# AMC_FMC_Carrier.net
KiCad netlist of a schematic drawn in Altium Designer
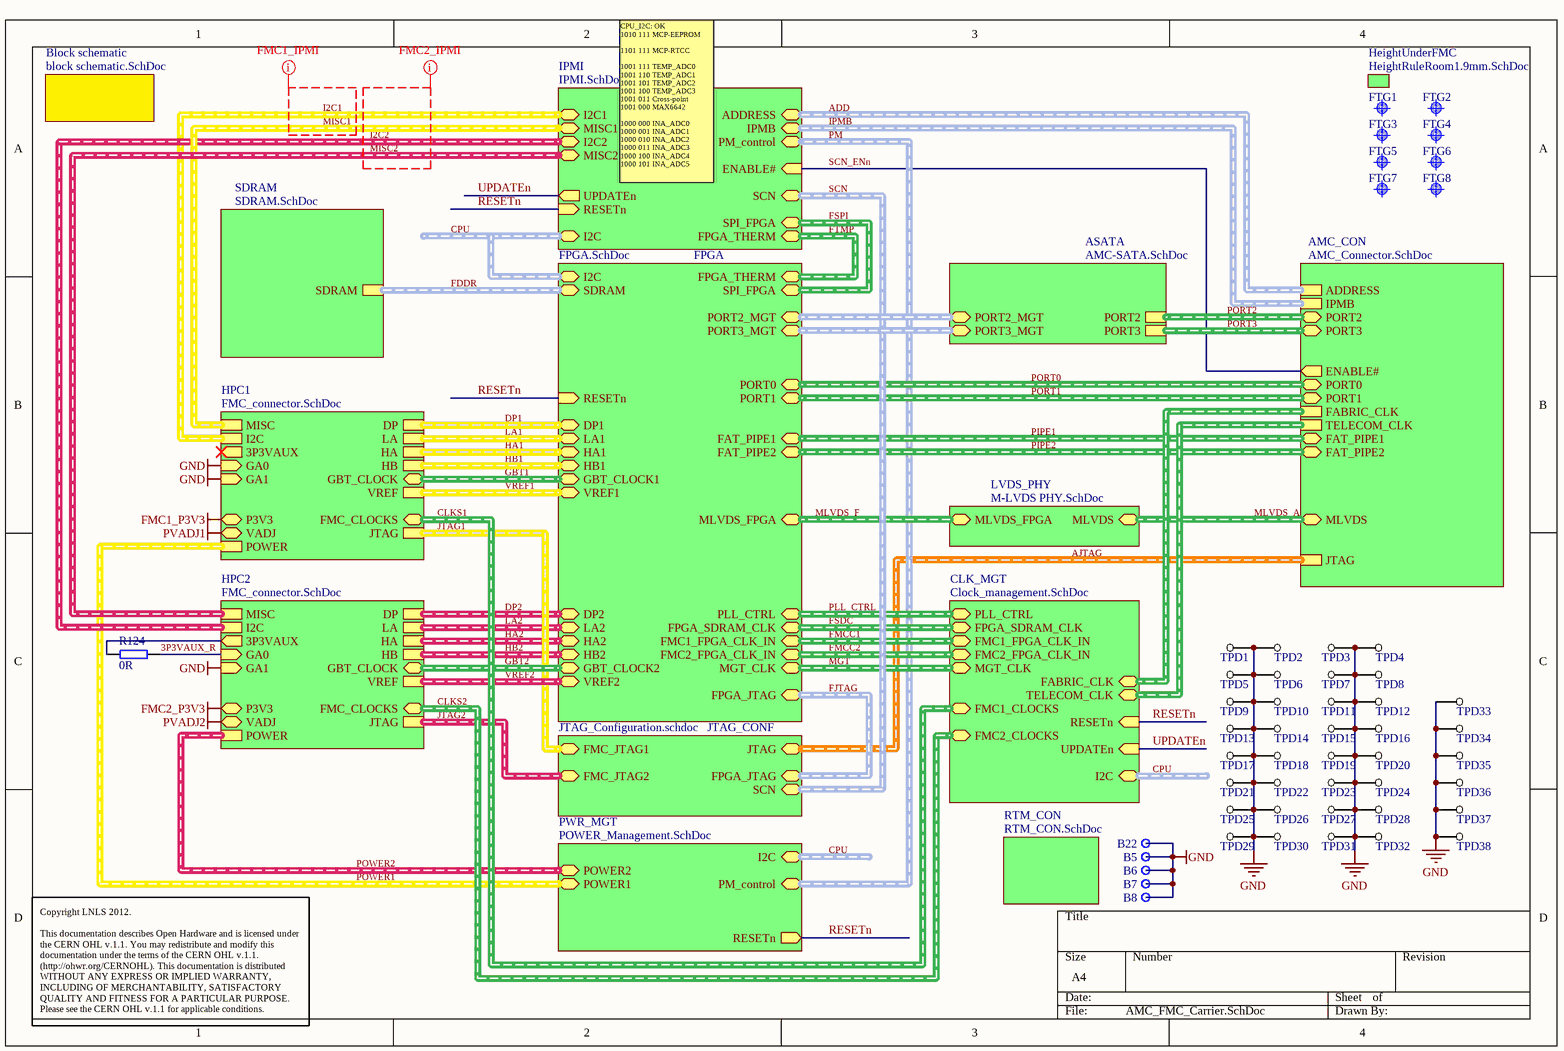
[diagram p0: AMC_FMC_Carrier.SchDoc]

(export (version "E")
  (design (tool "Eeschema 10.0.6"))
  (components
    (comp (ref "B5")
      (value "Test Point")
      (footprint "VERO_20-2136")
      (description "Single Terminal Socket")
      (fields
        (field (name "PART NUMBER") "VERO_20-2136")
        (field (name "MANUFACTURER") "VERO TECHNOLOGIES")
        (field (name "AUTHOR") "CERN DEM JLC")
      )
      (libsource (lib "Connectors") (part "Single Terminal Socket"))
    )
    (comp (ref "B6")
      (value "Test Point")
      (footprint "VERO_20-2136")
      (description "Single Terminal Socket")
      (fields
        (field (name "PART NUMBER") "VERO_20-2136")
        (field (name "MANUFACTURER") "VERO TECHNOLOGIES")
        (field (name "AUTHOR") "CERN DEM JLC")
      )
      (libsource (lib "Connectors") (part "Single Terminal Socket"))
    )
    (comp (ref "B7")
      (value "Test Point")
      (footprint "VERO_20-2136")
      (description "Single Terminal Socket")
      (fields
        (field (name "PART NUMBER") "VERO_20-2136")
        (field (name "MANUFACTURER") "VERO TECHNOLOGIES")
        (field (name "AUTHOR") "CERN DEM JLC")
      )
      (libsource (lib "Connectors") (part "Single Terminal Socket"))
    )
    (comp (ref "B8")
      (value "Test Point")
      (footprint "VERO_20-2136")
      (description "Single Terminal Socket")
      (fields
        (field (name "PART NUMBER") "VERO_20-2136")
        (field (name "MANUFACTURER") "VERO TECHNOLOGIES")
        (field (name "AUTHOR") "CERN DEM JLC")
      )
      (libsource (lib "Connectors") (part "Single Terminal Socket"))
    )
    (comp (ref "B22")
      (value "Test Point")
      (footprint "VERO_20-2136")
      (description "Single Terminal Socket")
      (fields
        (field (name "PART NUMBER") "VERO_20-2136")
        (field (name "MANUFACTURER") "VERO TECHNOLOGIES")
        (field (name "AUTHOR") "CERN DEM JLC")
      )
      (libsource (lib "Connectors") (part "Single Terminal Socket"))
    )
    (comp (ref "FTG1")
      (value "Use only in PCB")
      (footprint "FIDUCIAL_TOP_S100-200")
      (description "Fiducial Target")
      (fields (field (name "PART NUMBER") "FIDUCIAL_TARGET_S100-200") (field (name "AUTHOR") "CERN DEM JLC"))
      (libsource (lib "Eletro-mechanical") (part "Fiducial Target"))
    )
    (comp (ref "FTG2")
      (value "Use only in PCB")
      (footprint "FIDUCIAL_TOP_C100-200")
      (description "Fiducial Target")
      (fields (field (name "PART NUMBER") "FIDUCIAL_TARGET_C100-200") (field (name "AUTHOR") "CERN DEM JLC"))
      (libsource (lib "Eletro-mechanical") (part "Fiducial Target"))
    )
    (comp (ref "FTG3")
      (value "Use only in PCB")
      (footprint "FIDUCIAL_TOP_S100-200")
      (description "Fiducial Target")
      (fields (field (name "PART NUMBER") "FIDUCIAL_TARGET_S100-200") (field (name "AUTHOR") "CERN DEM JLC"))
      (libsource (lib "Eletro-mechanical") (part "Fiducial Target"))
    )
    (comp (ref "FTG4")
      (value "Use only in PCB")
      (footprint "FIDUCIAL_TOP_C100-200")
      (description "Fiducial Target")
      (fields (field (name "PART NUMBER") "FIDUCIAL_TARGET_C100-200") (field (name "AUTHOR") "CERN DEM JLC"))
      (libsource (lib "Eletro-mechanical") (part "Fiducial Target"))
    )
    (comp (ref "FTG5")
      (value "Use only in PCB")
      (footprint "FIDUCIAL_TOP_S100-200")
      (description "Fiducial Target")
      (fields (field (name "PART NUMBER") "FIDUCIAL_TARGET_S100-200") (field (name "AUTHOR") "CERN DEM JLC"))
      (libsource (lib "Eletro-mechanical") (part "Fiducial Target"))
    )
    (comp (ref "FTG6")
      (value "Use only in PCB")
      (footprint "FIDUCIAL_TOP_C100-200")
      (description "Fiducial Target")
      (fields (field (name "PART NUMBER") "FIDUCIAL_TARGET_C100-200") (field (name "AUTHOR") "CERN DEM JLC"))
      (libsource (lib "Eletro-mechanical") (part "Fiducial Target"))
    )
    (comp (ref "FTG7")
      (value "Use only in PCB")
      (footprint "FIDUCIAL_TOP_S100-200")
      (description "Fiducial Target")
      (fields (field (name "PART NUMBER") "FIDUCIAL_TARGET_S100-200") (field (name "AUTHOR") "CERN DEM JLC"))
      (libsource (lib "Eletro-mechanical") (part "Fiducial Target"))
    )
    (comp (ref "FTG8")
      (value "Use only in PCB")
      (footprint "FIDUCIAL_TOP_C100-200")
      (description "Fiducial Target")
      (fields (field (name "PART NUMBER") "FIDUCIAL_TARGET_C100-200") (field (name "AUTHOR") "CERN DEM JLC"))
      (libsource (lib "Eletro-mechanical") (part "Fiducial Target"))
    )
    (comp (ref "R124")
      (value "0R")
      (footprint "0402R")
      (description "SMD Resistor")
      (libsource (lib "LIBRARY_SCH") (part "RES_0402"))
    )
    (comp (ref "TPD1")
      (value "Test Point")
      (footprint "TP_DIFF_0805")
      (description "1625854-2")
      (fields (field (name "PART NUMBER") "TP_DIFF"))
      (libsource (lib "Markers") (part "TP_SMD_DIFF"))
    )
    (comp (ref "TPD2")
      (value "Test Point")
      (footprint "TP_DIFF_0805")
      (description "1625854-2")
      (fields (field (name "PART NUMBER") "TP_DIFF"))
      (libsource (lib "Markers") (part "TP_SMD_DIFF"))
    )
    (comp (ref "TPD3")
      (value "Test Point")
      (footprint "TP_DIFF_0805")
      (description "1625854-2")
      (fields (field (name "PART NUMBER") "TP_DIFF"))
      (libsource (lib "Markers") (part "TP_SMD_DIFF"))
    )
    (comp (ref "TPD4")
      (value "Test Point")
      (footprint "TP_DIFF_0805")
      (description "1625854-2")
      (fields (field (name "PART NUMBER") "TP_DIFF"))
      (libsource (lib "Markers") (part "TP_SMD_DIFF"))
    )
    (comp (ref "TPD5")
      (value "Test Point")
      (footprint "TP_DIFF_0805")
      (description "1625854-2")
      (fields (field (name "PART NUMBER") "TP_DIFF"))
      (libsource (lib "Markers") (part "TP_SMD_DIFF"))
    )
    (comp (ref "TPD6")
      (value "Test Point")
      (footprint "TP_DIFF_0805")
      (description "1625854-2")
      (fields (field (name "PART NUMBER") "TP_DIFF"))
      (libsource (lib "Markers") (part "TP_SMD_DIFF"))
    )
    (comp (ref "TPD7")
      (value "Test Point")
      (footprint "TP_DIFF_0805")
      (description "1625854-2")
      (fields (field (name "PART NUMBER") "TP_DIFF"))
      (libsource (lib "Markers") (part "TP_SMD_DIFF"))
    )
    (comp (ref "TPD8")
      (value "Test Point")
      (footprint "TP_DIFF_0805")
      (description "1625854-2")
      (fields (field (name "PART NUMBER") "TP_DIFF"))
      (libsource (lib "Markers") (part "TP_SMD_DIFF"))
    )
    (comp (ref "TPD9")
      (value "Test Point")
      (footprint "TP_DIFF_0805")
      (description "1625854-2")
      (fields (field (name "PART NUMBER") "TP_DIFF"))
      (libsource (lib "Markers") (part "TP_SMD_DIFF"))
    )
    (comp (ref "TPD10")
      (value "Test Point")
      (footprint "TP_DIFF_0805")
      (description "1625854-2")
      (fields (field (name "PART NUMBER") "TP_DIFF"))
      (libsource (lib "Markers") (part "TP_SMD_DIFF"))
    )
    (comp (ref "TPD11")
      (value "Test Point")
      (footprint "TP_DIFF_0805")
      (description "1625854-2")
      (fields (field (name "PART NUMBER") "TP_DIFF"))
      (libsource (lib "Markers") (part "TP_SMD_DIFF"))
    )
    (comp (ref "TPD12")
      (value "Test Point")
      (footprint "TP_DIFF_0805")
      (description "1625854-2")
      (fields (field (name "PART NUMBER") "TP_DIFF"))
      (libsource (lib "Markers") (part "TP_SMD_DIFF"))
    )
    (comp (ref "TPD13")
      (value "Test Point")
      (footprint "TP_DIFF_0805")
      (description "1625854-2")
      (fields (field (name "PART NUMBER") "TP_DIFF"))
      (libsource (lib "Markers") (part "TP_SMD_DIFF"))
    )
    (comp (ref "TPD14")
      (value "Test Point")
      (footprint "TP_DIFF_0805")
      (description "1625854-2")
      (fields (field (name "PART NUMBER") "TP_DIFF"))
      (libsource (lib "Markers") (part "TP_SMD_DIFF"))
    )
    (comp (ref "TPD15")
      (value "Test Point")
      (footprint "TP_DIFF_0805")
      (description "1625854-2")
      (fields (field (name "PART NUMBER") "TP_DIFF"))
      (libsource (lib "Markers") (part "TP_SMD_DIFF"))
    )
    (comp (ref "TPD16")
      (value "Test Point")
      (footprint "TP_DIFF_0805")
      (description "1625854-2")
      (fields (field (name "PART NUMBER") "TP_DIFF"))
      (libsource (lib "Markers") (part "TP_SMD_DIFF"))
    )
    (comp (ref "TPD17")
      (value "Test Point")
      (footprint "TP_DIFF_0805")
      (description "1625854-2")
      (fields (field (name "PART NUMBER") "TP_DIFF"))
      (libsource (lib "Markers") (part "TP_SMD_DIFF"))
    )
    (comp (ref "TPD18")
      (value "Test Point")
      (footprint "TP_DIFF_0805")
      (description "1625854-2")
      (fields (field (name "PART NUMBER") "TP_DIFF"))
      (libsource (lib "Markers") (part "TP_SMD_DIFF"))
    )
    (comp (ref "TPD19")
      (value "Test Point")
      (footprint "TP_DIFF_0805")
      (description "1625854-2")
      (fields (field (name "PART NUMBER") "TP_DIFF"))
      (libsource (lib "Markers") (part "TP_SMD_DIFF"))
    )
    (comp (ref "TPD20")
      (value "Test Point")
      (footprint "TP_DIFF_0805")
      (description "1625854-2")
      (fields (field (name "PART NUMBER") "TP_DIFF"))
      (libsource (lib "Markers") (part "TP_SMD_DIFF"))
    )
    (comp (ref "TPD21")
      (value "Test Point")
      (footprint "TP_DIFF_0805")
      (description "1625854-2")
      (fields (field (name "PART NUMBER") "TP_DIFF"))
      (libsource (lib "Markers") (part "TP_SMD_DIFF"))
    )
    (comp (ref "TPD22")
      (value "Test Point")
      (footprint "TP_DIFF_0805")
      (description "1625854-2")
      (fields (field (name "PART NUMBER") "TP_DIFF"))
      (libsource (lib "Markers") (part "TP_SMD_DIFF"))
    )
    (comp (ref "TPD23")
      (value "Test Point")
      (footprint "TP_DIFF_0805")
      (description "1625854-2")
      (fields (field (name "PART NUMBER") "TP_DIFF"))
      (libsource (lib "Markers") (part "TP_SMD_DIFF"))
    )
    (comp (ref "TPD24")
      (value "Test Point")
      (footprint "TP_DIFF_0805")
      (description "1625854-2")
      (fields (field (name "PART NUMBER") "TP_DIFF"))
      (libsource (lib "Markers") (part "TP_SMD_DIFF"))
    )
    (comp (ref "TPD25")
      (value "Test Point")
      (footprint "TP_DIFF_0805")
      (description "1625854-2")
      (fields (field (name "PART NUMBER") "TP_DIFF"))
      (libsource (lib "Markers") (part "TP_SMD_DIFF"))
    )
    (comp (ref "TPD26")
      (value "Test Point")
      (footprint "TP_DIFF_0805")
      (description "1625854-2")
      (fields (field (name "PART NUMBER") "TP_DIFF"))
      (libsource (lib "Markers") (part "TP_SMD_DIFF"))
    )
    (comp (ref "TPD27")
      (value "Test Point")
      (footprint "TP_DIFF_0805")
      (description "1625854-2")
      (fields (field (name "PART NUMBER") "TP_DIFF"))
      (libsource (lib "Markers") (part "TP_SMD_DIFF"))
    )
    (comp (ref "TPD28")
      (value "Test Point")
      (footprint "TP_DIFF_0805")
      (description "1625854-2")
      (fields (field (name "PART NUMBER") "TP_DIFF"))
      (libsource (lib "Markers") (part "TP_SMD_DIFF"))
    )
    (comp (ref "TPD29")
      (value "Test Point")
      (footprint "TP_DIFF_0805")
      (description "1625854-2")
      (fields (field (name "PART NUMBER") "TP_DIFF"))
      (libsource (lib "Markers") (part "TP_SMD_DIFF"))
    )
    (comp (ref "TPD30")
      (value "Test Point")
      (footprint "TP_DIFF_0805")
      (description "1625854-2")
      (fields (field (name "PART NUMBER") "TP_DIFF"))
      (libsource (lib "Markers") (part "TP_SMD_DIFF"))
    )
    (comp (ref "TPD31")
      (value "Test Point")
      (footprint "TP_DIFF_0805")
      (description "1625854-2")
      (fields (field (name "PART NUMBER") "TP_DIFF"))
      (libsource (lib "Markers") (part "TP_SMD_DIFF"))
    )
    (comp (ref "TPD32")
      (value "Test Point")
      (footprint "TP_DIFF_0805")
      (description "1625854-2")
      (fields (field (name "PART NUMBER") "TP_DIFF"))
      (libsource (lib "Markers") (part "TP_SMD_DIFF"))
    )
    (comp (ref "TPD33")
      (value "Test Point")
      (footprint "TP_DIFF_0805")
      (description "1625854-2")
      (fields (field (name "PART NUMBER") "TP_DIFF"))
      (libsource (lib "Markers") (part "TP_SMD_DIFF"))
    )
    (comp (ref "TPD34")
      (value "Test Point")
      (footprint "TP_DIFF_0805")
      (description "1625854-2")
      (fields (field (name "PART NUMBER") "TP_DIFF"))
      (libsource (lib "Markers") (part "TP_SMD_DIFF"))
    )
    (comp (ref "TPD35")
      (value "Test Point")
      (footprint "TP_DIFF_0805")
      (description "1625854-2")
      (fields (field (name "PART NUMBER") "TP_DIFF"))
      (libsource (lib "Markers") (part "TP_SMD_DIFF"))
    )
    (comp (ref "TPD36")
      (value "Test Point")
      (footprint "TP_DIFF_0805")
      (description "1625854-2")
      (fields (field (name "PART NUMBER") "TP_DIFF"))
      (libsource (lib "Markers") (part "TP_SMD_DIFF"))
    )
    (comp (ref "TPD37")
      (value "Test Point")
      (footprint "TP_DIFF_0805")
      (description "1625854-2")
      (fields (field (name "PART NUMBER") "TP_DIFF"))
      (libsource (lib "Markers") (part "TP_SMD_DIFF"))
    )
    (comp (ref "TPD38")
      (value "Test Point")
      (footprint "TP_DIFF_0805")
      (description "1625854-2")
      (fields (field (name "PART NUMBER") "TP_DIFF"))
      (libsource (lib "Markers") (part "TP_SMD_DIFF"))
    )
  )
  (nets
    (net (code "47") (name "/3P3VAUX_1") (class "Default")
      (node (ref "R124") (pin "1") (pinfunction "1_1") (pintype "passive"))
    )
    (net (code "48") (name "/3P3VAUX_R") (class "Default")
      (node (ref "R124") (pin "2") (pinfunction "2_2") (pintype "passive"))
    )
    (net (code "104") (name "GND") (class "Default")
      (node (ref "B22") (pin "1") (pinfunction "1_1") (pintype "bidirectional"))
      (node (ref "B5") (pin "1") (pinfunction "1_1") (pintype "bidirectional"))
      (node (ref "B6") (pin "1") (pinfunction "1_1") (pintype "bidirectional"))
      (node (ref "B7") (pin "1") (pinfunction "1_1") (pintype "bidirectional"))
      (node (ref "B8") (pin "1") (pinfunction "1_1") (pintype "bidirectional"))
      (node (ref "TPD1") (pin "1") (pinfunction "TP_1") (pintype "passive"))
      (node (ref "TPD10") (pin "1") (pinfunction "TP_1") (pintype "passive"))
      (node (ref "TPD11") (pin "1") (pinfunction "TP_1") (pintype "passive"))
      (node (ref "TPD12") (pin "1") (pinfunction "TP_1") (pintype "passive"))
      (node (ref "TPD13") (pin "1") (pinfunction "TP_1") (pintype "passive"))
      (node (ref "TPD14") (pin "1") (pinfunction "TP_1") (pintype "passive"))
      (node (ref "TPD15") (pin "1") (pinfunction "TP_1") (pintype "passive"))
      (node (ref "TPD16") (pin "1") (pinfunction "TP_1") (pintype "passive"))
      (node (ref "TPD17") (pin "1") (pinfunction "TP_1") (pintype "passive"))
      (node (ref "TPD18") (pin "1") (pinfunction "TP_1") (pintype "passive"))
      (node (ref "TPD19") (pin "1") (pinfunction "TP_1") (pintype "passive"))
      (node (ref "TPD2") (pin "1") (pinfunction "TP_1") (pintype "passive"))
      (node (ref "TPD20") (pin "1") (pinfunction "TP_1") (pintype "passive"))
      (node (ref "TPD21") (pin "1") (pinfunction "TP_1") (pintype "passive"))
      (node (ref "TPD22") (pin "1") (pinfunction "TP_1") (pintype "passive"))
      (node (ref "TPD23") (pin "1") (pinfunction "TP_1") (pintype "passive"))
      (node (ref "TPD24") (pin "1") (pinfunction "TP_1") (pintype "passive"))
      (node (ref "TPD25") (pin "1") (pinfunction "TP_1") (pintype "passive"))
      (node (ref "TPD26") (pin "1") (pinfunction "TP_1") (pintype "passive"))
      (node (ref "TPD27") (pin "1") (pinfunction "TP_1") (pintype "passive"))
      (node (ref "TPD28") (pin "1") (pinfunction "TP_1") (pintype "passive"))
      (node (ref "TPD29") (pin "1") (pinfunction "TP_1") (pintype "passive"))
      (node (ref "TPD3") (pin "1") (pinfunction "TP_1") (pintype "passive"))
      (node (ref "TPD30") (pin "1") (pinfunction "TP_1") (pintype "passive"))
      (node (ref "TPD31") (pin "1") (pinfunction "TP_1") (pintype "passive"))
      (node (ref "TPD32") (pin "1") (pinfunction "TP_1") (pintype "passive"))
      (node (ref "TPD33") (pin "1") (pinfunction "TP_1") (pintype "passive"))
      (node (ref "TPD34") (pin "1") (pinfunction "TP_1") (pintype "passive"))
      (node (ref "TPD35") (pin "1") (pinfunction "TP_1") (pintype "passive"))
      (node (ref "TPD36") (pin "1") (pinfunction "TP_1") (pintype "passive"))
      (node (ref "TPD37") (pin "1") (pinfunction "TP_1") (pintype "passive"))
      (node (ref "TPD38") (pin "1") (pinfunction "TP_1") (pintype "passive"))
      (node (ref "TPD4") (pin "1") (pinfunction "TP_1") (pintype "passive"))
      (node (ref "TPD5") (pin "1") (pinfunction "TP_1") (pintype "passive"))
      (node (ref "TPD6") (pin "1") (pinfunction "TP_1") (pintype "passive"))
      (node (ref "TPD7") (pin "1") (pinfunction "TP_1") (pintype "passive"))
      (node (ref "TPD8") (pin "1") (pinfunction "TP_1") (pintype "passive"))
      (node (ref "TPD9") (pin "1") (pinfunction "TP_1") (pintype "passive"))
    )
  )
)
